# Schematics.net
KiCad netlist of a schematic drawn in Altium Designer
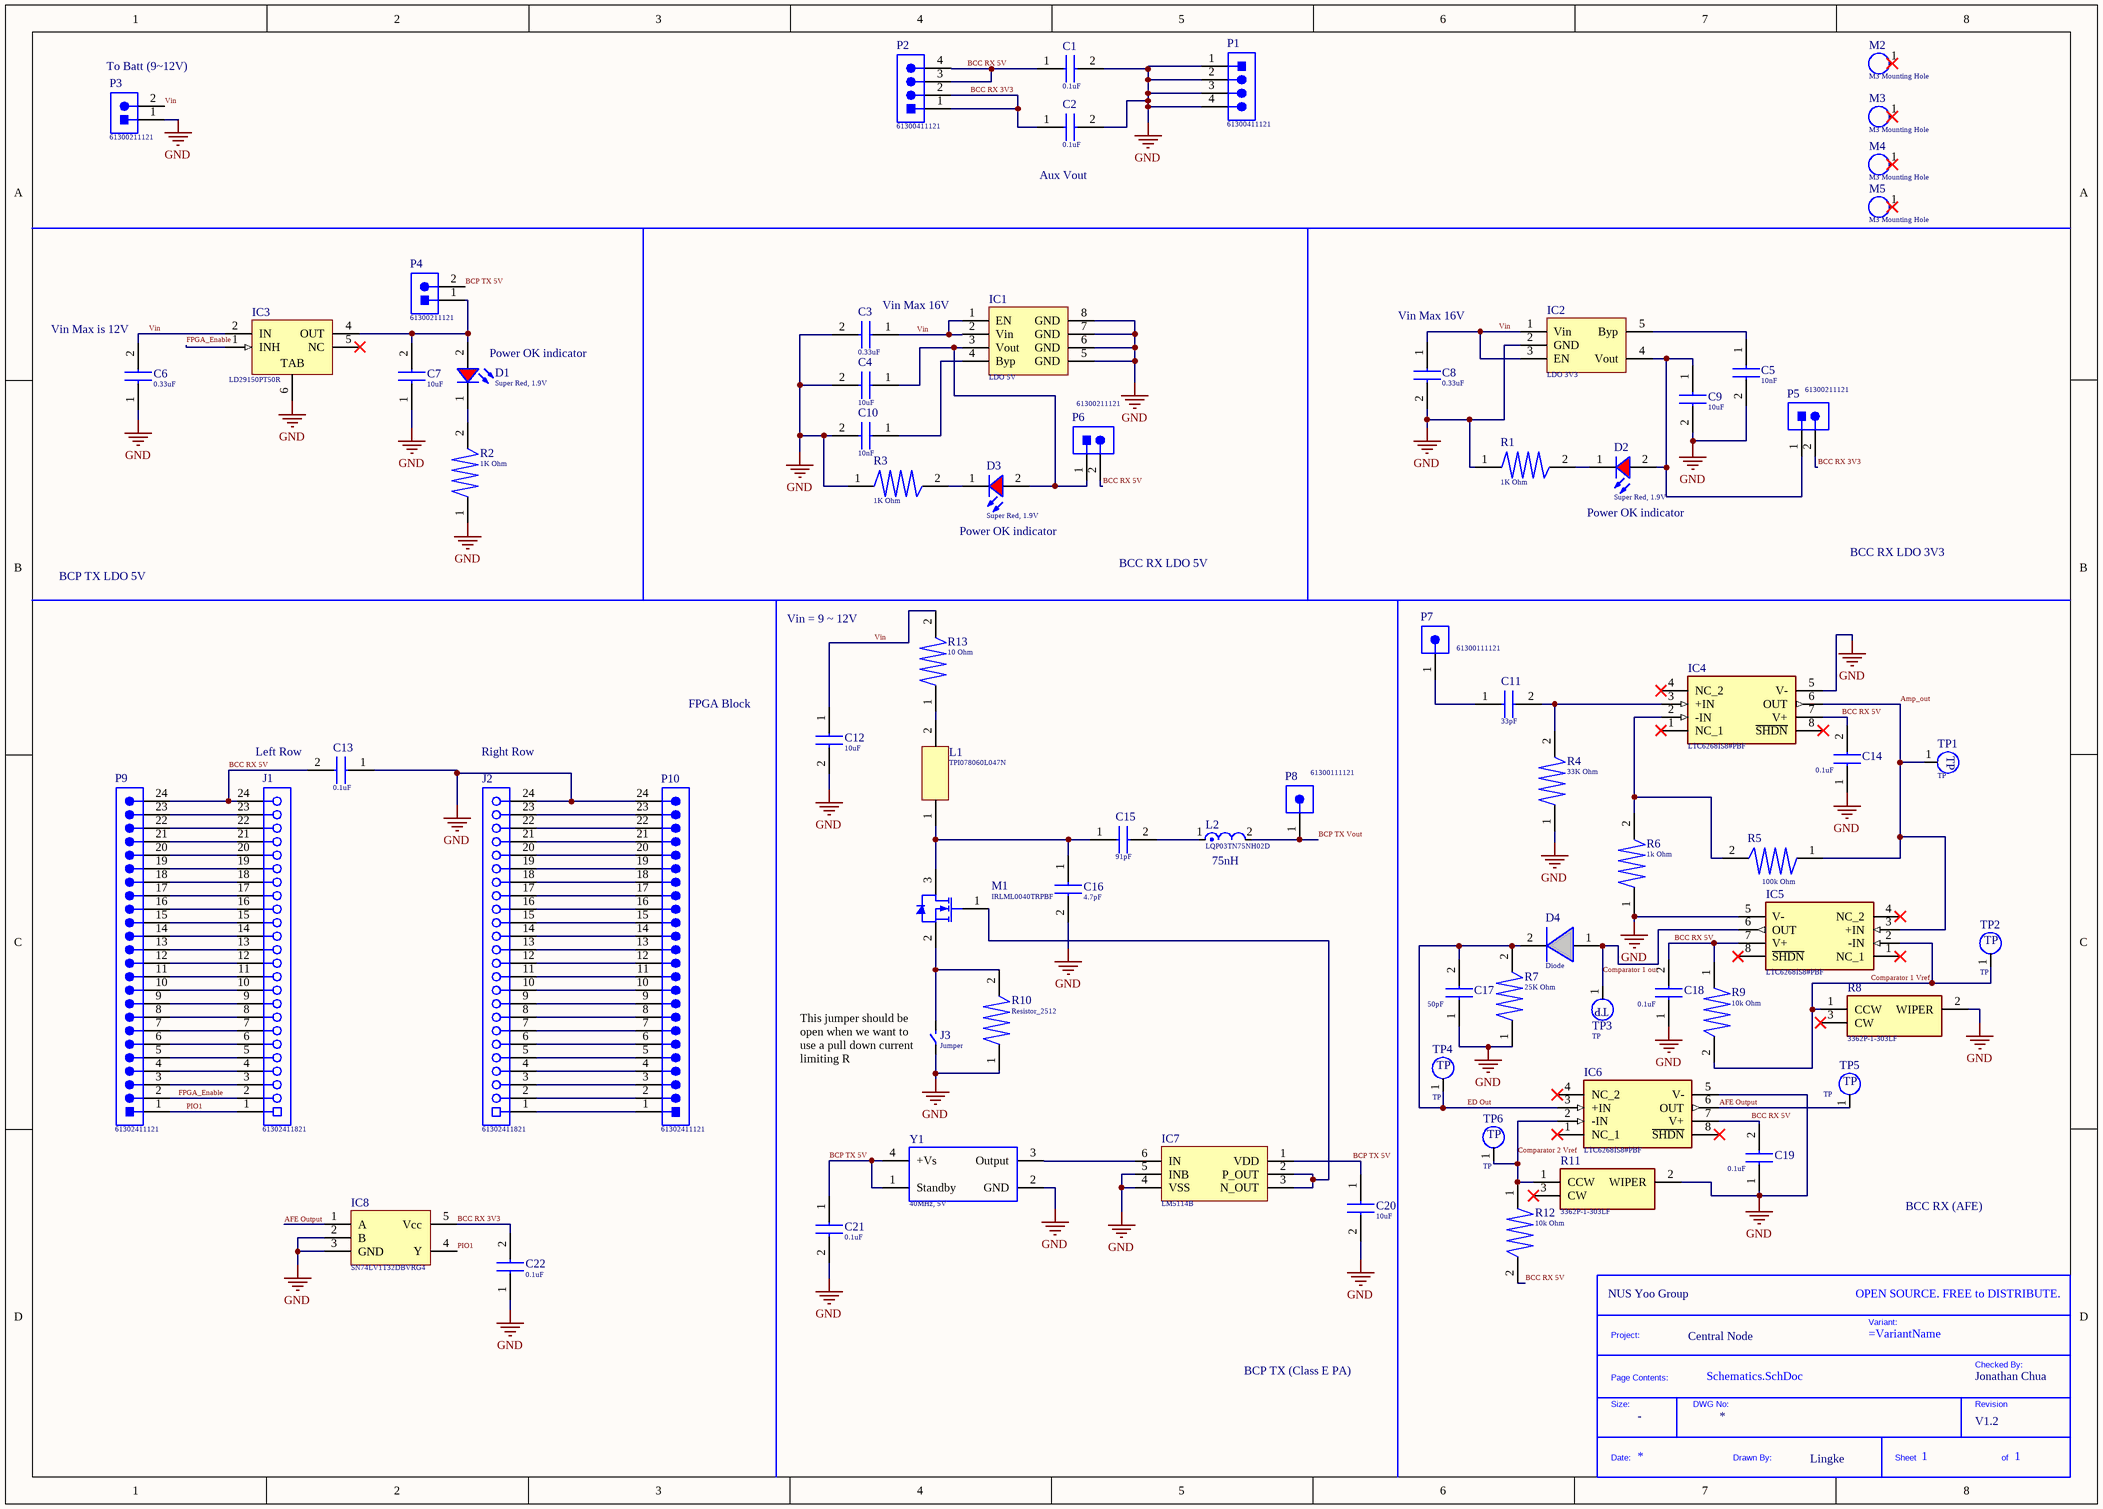
[diagram p0: Schematics.SchDoc]

(export (version "E")
  (design (tool "Eeschema 10.0.6"))
  (components
    (comp (ref "*")
      (value "Title_Block")
      (description "Standard Title Block.")
      (fields
        (field (name "PROJECT NAME") "Central Node")
        (field (name "COMPANY") "NUS Yoo Group")
        (field (name "DRAWN BY") "Lingke")
        (field (name "REVISION") "V1.2")
        (field (name "DWG NO") "*")
        (field (name "SIZE") "-")
        (field (name "CHECKED BY") "Jonathan Chua")
      )
      (libsource (lib "General Electronics") (part "Title_Block"))
    )
    (comp (ref "C1")
      (value "0.1uF")
      (footprint "0603")
      (description "Capacitor")
      (libsource (lib "General Electronics") (part "Capacitor_0603"))
    )
    (comp (ref "C2")
      (value "0.1uF")
      (footprint "0603")
      (description "Capacitor")
      (libsource (lib "General Electronics") (part "Capacitor_0603"))
    )
    (comp (ref "C3")
      (value "0.33uF")
      (footprint "0603")
      (description "Capacitor")
      (libsource (lib "General Electronics") (part "Capacitor_0603"))
    )
    (comp (ref "C4")
      (value "10uF")
      (footprint "0603")
      (description "Capacitor")
      (libsource (lib "General Electronics") (part "Capacitor_0603"))
    )
    (comp (ref "C5")
      (value "10nF")
      (footprint "0603")
      (description "Capacitor")
      (libsource (lib "General Electronics") (part "Capacitor_0603"))
    )
    (comp (ref "C6")
      (value "0.33uF")
      (footprint "0603")
      (description "Capacitor")
      (libsource (lib "General Electronics") (part "Capacitor_0603"))
    )
    (comp (ref "C7")
      (value "10uF")
      (footprint "0603")
      (description "Capacitor")
      (libsource (lib "General Electronics") (part "Capacitor_0603"))
    )
    (comp (ref "C8")
      (value "0.33uF")
      (footprint "0603")
      (description "Capacitor")
      (libsource (lib "General Electronics") (part "Capacitor_0603"))
    )
    (comp (ref "C9")
      (value "10uF")
      (footprint "0603")
      (description "Capacitor")
      (libsource (lib "General Electronics") (part "Capacitor_0603"))
    )
    (comp (ref "C10")
      (value "10nF")
      (footprint "0603")
      (description "Capacitor")
      (libsource (lib "General Electronics") (part "Capacitor_0603"))
    )
    (comp (ref "C11")
      (value "33pF")
      (footprint "0603")
      (description "Capacitor")
      (libsource (lib "General Electronics") (part "Capacitor_0603"))
    )
    (comp (ref "C12")
      (value "10uF")
      (footprint "0603")
      (description "Capacitor")
      (libsource (lib "General Electronics") (part "Capacitor_0603"))
    )
    (comp (ref "C13")
      (value "0.1uF")
      (footprint "0603")
      (description "Capacitor")
      (libsource (lib "General Electronics") (part "Capacitor_0603"))
    )
    (comp (ref "C14")
      (value "0.1uF")
      (footprint "0603")
      (description "Capacitor")
      (libsource (lib "General Electronics") (part "Capacitor_0603"))
    )
    (comp (ref "C15")
      (value "91pF")
      (footprint "0603")
      (description "Capacitor")
      (libsource (lib "General Electronics") (part "Capacitor_0603"))
    )
    (comp (ref "C16")
      (value "4.7pF")
      (footprint "0603")
      (description "Capacitor")
      (libsource (lib "General Electronics") (part "Capacitor_0603"))
    )
    (comp (ref "C17")
      (value "50pF")
      (footprint "0603")
      (description "Capacitor")
      (libsource (lib "General Electronics") (part "Capacitor_0603"))
    )
    (comp (ref "C18")
      (value "0.1uF")
      (footprint "0603")
      (description "Capacitor")
      (libsource (lib "General Electronics") (part "Capacitor_0603"))
    )
    (comp (ref "C19")
      (value "0.1uF")
      (footprint "0603")
      (description "Capacitor")
      (libsource (lib "General Electronics") (part "Capacitor_0603"))
    )
    (comp (ref "C20")
      (value "10uF")
      (footprint "0603")
      (description "Capacitor")
      (libsource (lib "General Electronics") (part "Capacitor_0603"))
    )
    (comp (ref "C21")
      (value "0.1uF")
      (footprint "0603")
      (description "Capacitor")
      (libsource (lib "General Electronics") (part "Capacitor_0603"))
    )
    (comp (ref "C22")
      (value "0.1uF")
      (footprint "0603")
      (description "Capacitor")
      (libsource (lib "General Electronics") (part "Capacitor_0603"))
    )
    (comp (ref "D1")
      (value "Super Red, 1.9V")
      (footprint "WL-SMCW_0603_H=0.7mm")
      (description "WL-SMCW SMT Mono-color Chip LED Waterclear, size 0603, Super Red, 1.9V, 140deg")
      (fields (field (name "PART NUMBER") "150060SS75000") (field (name "PUBLISHER") "Wurth Elektronik"))
      (libsource (lib "Altium_WL-SMCW (rev20a)") (part "150060SS75000"))
    )
    (comp (ref "D2")
      (value "Super Red, 1.9V")
      (footprint "WL-SMCW_0603_H=0.7mm")
      (description "WL-SMCW SMT Mono-color Chip LED Waterclear, size 0603, Super Red, 1.9V, 140deg")
      (fields (field (name "PART NUMBER") "150060SS75000") (field (name "PUBLISHER") "Wurth Elektronik"))
      (libsource (lib "Altium_WL-SMCW (rev20a)") (part "150060SS75000"))
    )
    (comp (ref "D3")
      (value "Super Red, 1.9V")
      (footprint "WL-SMCW_0603_H=0.7mm")
      (description "WL-SMCW SMT Mono-color Chip LED Waterclear, size 0603, Super Red, 1.9V, 140deg")
      (fields (field (name "PART NUMBER") "150060SS75000") (field (name "PUBLISHER") "Wurth Elektronik"))
      (libsource (lib "Altium_WL-SMCW (rev20a)") (part "150060SS75000"))
    )
    (comp (ref "D4") (value "Diode") (footprint "0603") (libsource (lib "FYP_BCC_BCP NUS") (part "Diode")))
    (comp (ref "IC1")
      (value "LDO 5V")
      (footprint "SOIC-8")
      (libsource (lib "FYP_BCC_BCP NUS") (part "SPX3819S-L-5-0/TR"))
    )
    (comp (ref "IC2")
      (value "LDO 3V3")
      (footprint "SOT-23-5")
      (libsource (lib "FYP_BCC_BCP NUS") (part "SPX3819M5-L-3-3/TR"))
    )
    (comp (ref "IC3")
      (value "LD29150PT50R")
      (footprint "PPAK_L")
      (description "1.5A, Very-Low Drop Voltage Regulator, 5V, 5-Pin PPAK")
      (libsource (lib "FYP_BCC_BCP NUS Symbol Library") (part "LD29150PT50R"))
    )
    (comp (ref "IC4")
      (value "LTC6268IS8#PBF")
      (footprint "SOIC127P599X175-8N")
      (description "Integrated Circuit")
      (fields (field (name "MOUSER2 PART NUMBER") "584-LTC6268IS8#PBF"))
      (libsource (lib "FYP_BCC_BCP NUS") (part "LTC6268IS8#PBF"))
    )
    (comp (ref "IC5")
      (value "LTC6268IS8#PBF")
      (footprint "SOIC127P599X175-8N")
      (description "Integrated Circuit")
      (fields (field (name "MOUSER2 PART NUMBER") "584-LTC6268IS8#PBF"))
      (libsource (lib "") (part "LTC6268IS8#PBF_1"))
    )
    (comp (ref "IC6")
      (value "LTC6268IS8#PBF")
      (footprint "SOIC127P599X175-8N")
      (description "Integrated Circuit")
      (fields (field (name "MOUSER2 PART NUMBER") "584-LTC6268IS8#PBF"))
      (libsource (lib "FYP_BCC_BCP NUS") (part "LTC6268IS8#PBF"))
    )
    (comp (ref "IC7")
      (value "LM5114B")
      (footprint "SOT-23-6")
      (libsource (lib "FYP_BCC_BCP NUS") (part "LM5114B"))
    )
    (comp (ref "IC8")
      (value "SN74LV1T32DBVRG4")
      (footprint "SOT-23-5")
      (libsource (lib "FYP_BCC_BCP NUS") (part "SN74LV1T32DBVRG4"))
    )
    (comp (ref "J1")
      (value "61302411821")
      (footprint "61302411821")
      (description "WR-PHD Socket Header, THT, pitch 2.54mm, Single Row, Vertical, 24p")
      (fields (field (name "MANUFACTURER") "Wurth Elektronik"))
      (libsource (lib "Altium_WR-PHD (rev22a)") (part "61302411821"))
    )
    (comp (ref "J2")
      (value "61302411821")
      (footprint "61302411821")
      (description "WR-PHD Socket Header, THT, pitch 2.54mm, Single Row, Vertical, 24p")
      (fields (field (name "MANUFACTURER") "Wurth Elektronik"))
      (libsource (lib "Altium_WR-PHD (rev22a)") (part "61302411821"))
    )
    (comp (ref "J3")
      (value "Jumper")
      (footprint "0603")
      (description "Capacitor")
      (libsource (lib "General Electronics") (part "0603_Jumper"))
    )
    (comp (ref "L1")
      (value "TPI078060L047N")
      (footprint "TPI078060L047N")
      (libsource (lib "FYP_BCC_BCP NUS") (part "TPI078060L047N"))
    )
    (comp (ref "L2")
      (value "LQP03TN75NH02D")
      (footprint "FP-LQP03PN_02-IPC_A")
      (description "Film type RF Inductor 75nH ±3% 100mA 10Ω 0201 (0603)")
      (fields (field (name "TOLERANCE") "3%"))
      (libsource (lib "FYP_BCC_BCP NUS") (part "LQP03TN75NH02D"))
    )
    (comp (ref "M1")
      (value "IRLML0040TRPBF")
      (footprint "SOT-23")
      (description "HEXFET(R) Power MOSFET, 40 V, -55 to 150 degC, 3-Pin SOT-23, RoHS, Tape and Reel")
      (fields (field (name "MANUFACTURER") "International Rectifier"))
      (libsource (lib "FYP_BCC_BCP NUS") (part "IRLML0040TRPBF"))
    )
    (comp (ref "M2")
      (value "M3 Mounting Hole")
      (footprint "M3 Hole")
      (libsource (lib "General Electronics") (part "M3_Mounting_hole"))
    )
    (comp (ref "M3")
      (value "M3 Mounting Hole")
      (footprint "M3 Hole")
      (libsource (lib "General Electronics") (part "M3_Mounting_hole"))
    )
    (comp (ref "M4")
      (value "M3 Mounting Hole")
      (footprint "M3 Hole")
      (libsource (lib "General Electronics") (part "M3_Mounting_hole"))
    )
    (comp (ref "M5")
      (value "M3 Mounting Hole")
      (footprint "M3 Hole")
      (libsource (lib "General Electronics") (part "M3_Mounting_hole"))
    )
    (comp (ref "P1")
      (value "61300411121")
      (footprint "61300411121")
      (description "WR-PHD Pin Header, THT, pitch 2.54mm, Single Row, Vertical, 4p")
      (fields (field (name "MANUFACTURER") "Wurth Elektronik"))
      (libsource (lib "") (part "61300411121_1"))
    )
    (comp (ref "P2")
      (value "61300411121")
      (footprint "61300411121")
      (description "WR-PHD Pin Header, THT, pitch 2.54mm, Single Row, Vertical, 4p")
      (fields (field (name "MANUFACTURER") "Wurth Elektronik"))
      (libsource (lib "Altium_WR-PHD (rev22a)") (part "61300411121"))
    )
    (comp (ref "P3")
      (value "61300211121")
      (footprint "61300211121")
      (description "WR-PHD Pin Header, THT, pitch 2.54mm, Single Row, Vertical, 2p")
      (fields (field (name "MANUFACTURER") "Wurth Elektronik"))
      (libsource (lib "Altium_WR-PHD (rev22a)") (part "61300211121"))
    )
    (comp (ref "P4")
      (value "61300211121")
      (footprint "61300211121")
      (description "WR-PHD Pin Header, THT, pitch 2.54mm, Single Row, Vertical, 2p")
      (fields (field (name "MANUFACTURER") "Wurth Elektronik"))
      (libsource (lib "Altium_WR-PHD (rev22a)") (part "61300211121"))
    )
    (comp (ref "P5")
      (value "61300211121")
      (footprint "61300211121")
      (description "WR-PHD Pin Header, THT, pitch 2.54mm, Single Row, Vertical, 2p")
      (fields (field (name "MANUFACTURER") "Wurth Elektronik"))
      (libsource (lib "") (part "61300211121_1"))
    )
    (comp (ref "P6")
      (value "61300211121")
      (footprint "61300211121")
      (description "WR-PHD Pin Header, THT, pitch 2.54mm, Single Row, Vertical, 2p")
      (fields (field (name "MANUFACTURER") "Wurth Elektronik"))
      (libsource (lib "") (part "61300211121_1"))
    )
    (comp (ref "P7")
      (value "61300111121")
      (footprint "61300111121")
      (description "WR-PHD Pin Header, THT, pitch 2.54mm, Single Row, Vertical, 1p")
      (fields (field (name "MANUFACTURER") "Wurth Elektronik"))
      (libsource (lib "Altium_WR-PHD (rev22a)") (part "61300111121"))
    )
    (comp (ref "P8")
      (value "61300111121")
      (footprint "61300111121")
      (description "WR-PHD Pin Header, THT, pitch 2.54mm, Single Row, Vertical, 1p")
      (fields (field (name "MANUFACTURER") "Wurth Elektronik"))
      (libsource (lib "Altium_WR-PHD (rev22a)") (part "61300111121"))
    )
    (comp (ref "P9")
      (value "61302411121")
      (footprint "61302411121")
      (description "WR-PHD Pin Header, THT, pitch 2.54mm, Single Row, Vertical, 24p")
      (fields (field (name "MANUFACTURER") "Wurth Elektronik"))
      (libsource (lib "Altium_WR-PHD (rev22a)") (part "61302411121"))
    )
    (comp (ref "P10")
      (value "61302411121")
      (footprint "61302411121")
      (description "WR-PHD Pin Header, THT, pitch 2.54mm, Single Row, Vertical, 24p")
      (fields (field (name "MANUFACTURER") "Wurth Elektronik"))
      (libsource (lib "Altium_WR-PHD (rev22a)") (part "61302411121"))
    )
    (comp (ref "R1")
      (value "1K Ohm")
      (footprint "0603")
      (description "Resistor")
      (libsource (lib "General Electronics") (part "Resistor"))
    )
    (comp (ref "R2")
      (value "1K Ohm")
      (footprint "0603")
      (description "Resistor")
      (libsource (lib "General Electronics") (part "Resistor"))
    )
    (comp (ref "R3")
      (value "1K Ohm")
      (footprint "0603")
      (description "Resistor")
      (libsource (lib "General Electronics") (part "Resistor"))
    )
    (comp (ref "R4")
      (value "33K Ohm")
      (footprint "0603")
      (description "Resistor")
      (libsource (lib "General Electronics") (part "Resistor"))
    )
    (comp (ref "R5")
      (value "100k Ohm")
      (footprint "0603")
      (description "Resistor")
      (libsource (lib "General Electronics") (part "Resistor"))
    )
    (comp (ref "R6")
      (value "1k Ohm")
      (footprint "0603")
      (description "Resistor")
      (libsource (lib "General Electronics") (part "Resistor"))
    )
    (comp (ref "R7")
      (value "25K Ohm")
      (footprint "0603")
      (description "Resistor")
      (libsource (lib "General Electronics") (part "Resistor"))
    )
    (comp (ref "R8")
      (value "3362P-1-303LF")
      (footprint "3362P_1")
      (description "Resistor")
      (libsource (lib "FYP_BCC_BCP NUS") (part "3362P-1-303LF"))
    )
    (comp (ref "R9")
      (value "10k Ohm")
      (footprint "0603")
      (description "Resistor")
      (libsource (lib "General Electronics") (part "Resistor"))
    )
    (comp (ref "R10")
      (value "Resistor_2512")
      (footprint "2512")
      (description "Resistor")
      (libsource (lib "General Electronics") (part "Resistor_2512"))
    )
    (comp (ref "R11")
      (value "3362P-1-303LF")
      (footprint "3362P_1")
      (description "Resistor")
      (libsource (lib "FYP_BCC_BCP NUS") (part "3362P-1-303LF"))
    )
    (comp (ref "R12")
      (value "10k Ohm")
      (footprint "0603")
      (description "Resistor")
      (libsource (lib "General Electronics") (part "Resistor"))
    )
    (comp (ref "R13")
      (value "10 Ohm")
      (footprint "2512")
      (description "Resistor")
      (libsource (lib "General Electronics") (part "Resistor_2512"))
    )
    (comp (ref "TP1")
      (value "TP")
      (footprint "Test Point")
      (description "Test Point 1mm by 1mm")
      (libsource (lib "General Electronics") (part "Test Point"))
    )
    (comp (ref "TP2")
      (value "TP")
      (footprint "Test Point")
      (description "Test Point 1mm by 1mm")
      (libsource (lib "General Electronics") (part "Test Point"))
    )
    (comp (ref "TP3")
      (value "TP")
      (footprint "Test Point")
      (description "Test Point 1mm by 1mm")
      (libsource (lib "General Electronics") (part "Test Point"))
    )
    (comp (ref "TP4")
      (value "TP")
      (footprint "Test Point")
      (description "Test Point 1mm by 1mm")
      (libsource (lib "General Electronics") (part "Test Point"))
    )
    (comp (ref "TP5")
      (value "TP")
      (footprint "Test Point")
      (description "Test Point 1mm by 1mm")
      (libsource (lib "General Electronics") (part "Test Point"))
    )
    (comp (ref "TP6")
      (value "TP")
      (footprint "Test Point")
      (description "Test Point 1mm by 1mm")
      (libsource (lib "General Electronics") (part "Test Point"))
    )
    (comp (ref "Y1")
      (value "40MHz, 5V")
      (footprint "WE-SPXO_CFPS-72")
      (description "WE-SPXO Simple Packaged Quartz Oscillator, SMT, CFPS-72, 40MHz, 5V")
      (fields
        (field (name "MANUFACTURER") "Wurth Elektronik")
        (field (name "MANUFACTURER PART NUMBER") "831018739")
      )
      (libsource (lib "Altium_WE-SPXO (rev20c)") (part "831018739"))
    )
  )
  (nets
    (net (code "1") (name "/AFE Output") (class "Default")
      (node (ref "IC6") (pin "6") (pinfunction "OUT_6") (pintype "output"))
      (node (ref "IC8") (pin "1") (pinfunction "A_1") (pintype "passive"))
      (node (ref "TP5") (pin "1") (pinfunction "TP_1") (pintype "passive"))
    )
    (net (code "2") (name "/Amp_out") (class "Default")
      (node (ref "IC4") (pin "6") (pinfunction "OUT_6") (pintype "output"))
      (node (ref "IC5") (pin "3") (pinfunction "+IN_3") (pintype "input"))
      (node (ref "R5") (pin "1") (pintype "passive"))
      (node (ref "TP1") (pin "1") (pinfunction "TP_1") (pintype "passive"))
    )
    (net (code "3") (name "/BCC RX 3V3") (class "Default")
      (node (ref "C2") (pin "1") (pinfunction "1_1") (pintype "passive"))
      (node (ref "C22") (pin "2") (pinfunction "2_2") (pintype "passive"))
      (node (ref "IC8") (pin "5") (pinfunction "Vcc_5") (pintype "passive"))
      (node (ref "P2") (pin "1") (pinfunction "1_1") (pintype "passive"))
      (node (ref "P2") (pin "2") (pinfunction "2_2") (pintype "passive"))
      (node (ref "P5") (pin "2") (pinfunction "2_2") (pintype "passive"))
    )
    (net (code "4") (name "/BCC RX 5V") (class "Default")
      (node (ref "C1") (pin "1") (pinfunction "1_1") (pintype "passive"))
      (node (ref "C13") (pin "2") (pinfunction "2_2") (pintype "passive"))
      (node (ref "C14") (pin "2") (pinfunction "2_2") (pintype "passive"))
      (node (ref "C18") (pin "2") (pinfunction "2_2") (pintype "passive"))
      (node (ref "C19") (pin "2") (pinfunction "2_2") (pintype "passive"))
      (node (ref "IC4") (pin "7") (pinfunction "V+_7") (pintype "passive"))
      (node (ref "IC5") (pin "7") (pinfunction "V+_7") (pintype "passive"))
      (node (ref "IC6") (pin "7") (pinfunction "V+_7") (pintype "passive"))
      (node (ref "J1") (pin "24") (pinfunction "24_24") (pintype "passive"))
      (node (ref "P2") (pin "3") (pinfunction "3_3") (pintype "passive"))
      (node (ref "P2") (pin "4") (pinfunction "4_4") (pintype "passive"))
      (node (ref "P6") (pin "2") (pinfunction "2_2") (pintype "passive"))
      (node (ref "P9") (pin "24") (pinfunction "24_24") (pintype "passive"))
      (node (ref "R12") (pin "2") (pintype "passive"))
      (node (ref "R9") (pin "1") (pintype "passive"))
    )
    (net (code "5") (name "/BCP TX 5V") (class "Default")
      (node (ref "C20") (pin "1") (pinfunction "1_1") (pintype "passive"))
      (node (ref "C21") (pin "1") (pinfunction "1_1") (pintype "passive"))
      (node (ref "IC7") (pin "1") (pinfunction "VDD_1") (pintype "passive"))
      (node (ref "P4") (pin "2") (pinfunction "2_2") (pintype "passive"))
      (node (ref "Y1") (pin "1") (pinfunction "Standby_1") (pintype "passive"))
      (node (ref "Y1") (pin "4") (pinfunction "+Vs_4") (pintype "passive"))
    )
    (net (code "6") (name "/BCP TX Vout") (class "Default")
      (node (ref "L2") (pin "2") (pinfunction "2_2") (pintype "passive"))
      (node (ref "P8") (pin "1") (pinfunction "1_1") (pintype "passive"))
    )
    (net (code "7") (name "/Comparator 1 Vref") (class "Default")
      (node (ref "IC5") (pin "2") (pinfunction "-IN_2") (pintype "input"))
      (node (ref "R8") (pin "1") (pinfunction "CCW_1") (pintype "passive"))
      (node (ref "R9") (pin "2") (pintype "passive"))
      (node (ref "TP2") (pin "1") (pinfunction "TP_1") (pintype "passive"))
    )
    (net (code "8") (name "/Comparator 1 out") (class "Default")
      (node (ref "D4") (pin "1") (pintype "passive"))
      (node (ref "IC5") (pin "6") (pinfunction "OUT_6") (pintype "output"))
      (node (ref "TP3") (pin "1") (pinfunction "TP_1") (pintype "passive"))
    )
    (net (code "9") (name "/Comparator 2 Vref") (class "Default")
      (node (ref "IC6") (pin "2") (pinfunction "-IN_2") (pintype "input"))
      (node (ref "R11") (pin "1") (pinfunction "CCW_1") (pintype "passive"))
      (node (ref "R12") (pin "1") (pintype "passive"))
      (node (ref "TP6") (pin "1") (pinfunction "TP_1") (pintype "passive"))
    )
    (net (code "10") (name "/ED Out") (class "Default")
      (node (ref "C17") (pin "2") (pinfunction "2_2") (pintype "passive"))
      (node (ref "D4") (pin "2") (pintype "passive"))
      (node (ref "IC6") (pin "3") (pinfunction "+IN_3") (pintype "input"))
      (node (ref "R7") (pin "2") (pintype "passive"))
      (node (ref "TP4") (pin "1") (pinfunction "TP_1") (pintype "passive"))
    )
    (net (code "11") (name "/FPGA_Enable") (class "Default")
      (node (ref "IC3") (pin "1") (pinfunction "INH_1") (pintype "input"))
      (node (ref "J1") (pin "2") (pinfunction "2_2") (pintype "passive"))
      (node (ref "P9") (pin "2") (pinfunction "2_2") (pintype "passive"))
    )
    (net (code "12") (name "/PIO1") (class "Default")
      (node (ref "IC8") (pin "4") (pinfunction "Y_4") (pintype "passive"))
      (node (ref "J1") (pin "1") (pinfunction "1_1") (pintype "passive"))
      (node (ref "P9") (pin "1") (pinfunction "1_1") (pintype "passive"))
    )
    (net (code "13") (name "/Vin") (class "Default")
      (node (ref "C12") (pin "1") (pinfunction "1_1") (pintype "passive"))
      (node (ref "C3") (pin "1") (pinfunction "1_1") (pintype "passive"))
      (node (ref "C6") (pin "2") (pinfunction "2_2") (pintype "passive"))
      (node (ref "C8") (pin "1") (pinfunction "1_1") (pintype "passive"))
      (node (ref "IC1") (pin "1") (pinfunction "EN_1") (pintype "passive"))
      (node (ref "IC1") (pin "2") (pinfunction "Vin_2") (pintype "passive"))
      (node (ref "IC2") (pin "1") (pinfunction "Vin_1") (pintype "passive"))
      (node (ref "IC2") (pin "3") (pinfunction "EN_3") (pintype "passive"))
      (node (ref "IC3") (pin "2") (pinfunction "IN_2") (pintype "power_in"))
      (node (ref "P3") (pin "2") (pinfunction "2_2") (pintype "passive"))
      (node (ref "R13") (pin "2") (pintype "passive"))
    )
    (net (code "14") (name "GND") (class "Default")
      (node (ref "C1") (pin "2") (pinfunction "2_2") (pintype "passive"))
      (node (ref "C10") (pin "2") (pinfunction "2_2") (pintype "passive"))
      (node (ref "C12") (pin "2") (pinfunction "2_2") (pintype "passive"))
      (node (ref "C13") (pin "1") (pinfunction "1_1") (pintype "passive"))
      (node (ref "C14") (pin "1") (pinfunction "1_1") (pintype "passive"))
      (node (ref "C16") (pin "2") (pinfunction "2_2") (pintype "passive"))
      (node (ref "C17") (pin "1") (pinfunction "1_1") (pintype "passive"))
      (node (ref "C18") (pin "1") (pinfunction "1_1") (pintype "passive"))
      (node (ref "C19") (pin "1") (pinfunction "1_1") (pintype "passive"))
      (node (ref "C2") (pin "2") (pinfunction "2_2") (pintype "passive"))
      (node (ref "C20") (pin "2") (pinfunction "2_2") (pintype "passive"))
      (node (ref "C21") (pin "2") (pinfunction "2_2") (pintype "passive"))
      (node (ref "C22") (pin "1") (pinfunction "1_1") (pintype "passive"))
      (node (ref "C3") (pin "2") (pinfunction "2_2") (pintype "passive"))
      (node (ref "C4") (pin "2") (pinfunction "2_2") (pintype "passive"))
      (node (ref "C5") (pin "2") (pinfunction "2_2") (pintype "passive"))
      (node (ref "C6") (pin "1") (pinfunction "1_1") (pintype "passive"))
      (node (ref "C7") (pin "1") (pinfunction "1_1") (pintype "passive"))
      (node (ref "C8") (pin "2") (pinfunction "2_2") (pintype "passive"))
      (node (ref "C9") (pin "2") (pinfunction "2_2") (pintype "passive"))
      (node (ref "IC1") (pin "5") (pinfunction "GND_5") (pintype "passive"))
      (node (ref "IC1") (pin "6") (pinfunction "GND_6") (pintype "passive"))
      (node (ref "IC1") (pin "7") (pinfunction "GND_7") (pintype "passive"))
      (node (ref "IC1") (pin "8") (pinfunction "GND_8") (pintype "passive"))
      (node (ref "IC2") (pin "2") (pinfunction "GND_2") (pintype "passive"))
      (node (ref "IC3") (pin "6") (pinfunction "TAB_6") (pintype "passive"))
      (node (ref "IC4") (pin "5") (pinfunction "V-_5") (pintype "passive"))
      (node (ref "IC5") (pin "5") (pinfunction "V-_5") (pintype "passive"))
      (node (ref "IC6") (pin "5") (pinfunction "V-_5") (pintype "passive"))
      (node (ref "IC7") (pin "4") (pinfunction "VSS_4") (pintype "passive"))
      (node (ref "IC7") (pin "5") (pinfunction "INB_5") (pintype "passive"))
      (node (ref "IC8") (pin "2") (pinfunction "B_2") (pintype "passive"))
      (node (ref "IC8") (pin "3") (pinfunction "GND_3") (pintype "passive"))
      (node (ref "J2") (pin "24") (pinfunction "24_24") (pintype "passive"))
      (node (ref "J3") (pin "1") (pinfunction "1_1") (pintype "passive"))
      (node (ref "P1") (pin "1") (pinfunction "1_1") (pintype "passive"))
      (node (ref "P1") (pin "2") (pinfunction "2_2") (pintype "passive"))
      (node (ref "P1") (pin "3") (pinfunction "3_3") (pintype "passive"))
      (node (ref "P1") (pin "4") (pinfunction "4_4") (pintype "passive"))
      (node (ref "P10") (pin "24") (pinfunction "24_24") (pintype "passive"))
      (node (ref "P3") (pin "1") (pinfunction "1_1") (pintype "passive"))
      (node (ref "R1") (pin "1") (pintype "passive"))
      (node (ref "R10") (pin "1") (pintype "passive"))
      (node (ref "R11") (pin "2") (pinfunction "WIPER_2") (pintype "passive"))
      (node (ref "R2") (pin "1") (pintype "passive"))
      (node (ref "R3") (pin "1") (pintype "passive"))
      (node (ref "R4") (pin "1") (pintype "passive"))
      (node (ref "R6") (pin "1") (pintype "passive"))
      (node (ref "R7") (pin "1") (pintype "passive"))
      (node (ref "R8") (pin "2") (pinfunction "WIPER_2") (pintype "passive"))
      (node (ref "Y1") (pin "2") (pinfunction "GND_2") (pintype "passive"))
    )
    (net (code "15") (name "Net-(C11-Pad1)") (class "Default")
      (node (ref "C11") (pin "1") (pinfunction "1_1") (pintype "passive"))
      (node (ref "P7") (pin "1") (pinfunction "1_1") (pintype "passive"))
    )
    (net (code "16") (name "Net-(C15-Pad2)") (class "Default")
      (node (ref "C15") (pin "2") (pinfunction "2_2") (pintype "passive"))
      (node (ref "L2") (pin "1") (pinfunction "1_1") (pintype "passive"))
    )
    (net (code "17") (name "Net-(D1-A)") (class "Default")
      (node (ref "C7") (pin "2") (pinfunction "2_2") (pintype "passive"))
      (node (ref "D1") (pin "2") (pinfunction "A_2") (pintype "passive"))
      (node (ref "IC3") (pin "4") (pinfunction "OUT_4") (pintype "power_in"))
      (node (ref "P4") (pin "1") (pinfunction "1_1") (pintype "passive"))
    )
    (net (code "18") (name "Net-(D1-K)") (class "Default")
      (node (ref "D1") (pin "1") (pinfunction "K_1") (pintype "passive"))
      (node (ref "R2") (pin "2") (pintype "passive"))
    )
    (net (code "19") (name "Net-(D2-A)") (class "Default")
      (node (ref "C9") (pin "1") (pinfunction "1_1") (pintype "passive"))
      (node (ref "D2") (pin "2") (pinfunction "A_2") (pintype "passive"))
      (node (ref "IC2") (pin "4") (pinfunction "Vout_4") (pintype "passive"))
      (node (ref "P5") (pin "1") (pinfunction "1_1") (pintype "passive"))
    )
    (net (code "20") (name "Net-(D2-K)") (class "Default")
      (node (ref "D2") (pin "1") (pinfunction "K_1") (pintype "passive"))
      (node (ref "R1") (pin "2") (pintype "passive"))
    )
    (net (code "21") (name "Net-(D3-A)") (class "Default")
      (node (ref "C4") (pin "1") (pinfunction "1_1") (pintype "passive"))
      (node (ref "D3") (pin "2") (pinfunction "A_2") (pintype "passive"))
      (node (ref "IC1") (pin "3") (pinfunction "Vout_3") (pintype "passive"))
      (node (ref "P6") (pin "1") (pinfunction "1_1") (pintype "passive"))
    )
    (net (code "22") (name "Net-(D3-K)") (class "Default")
      (node (ref "D3") (pin "1") (pinfunction "K_1") (pintype "passive"))
      (node (ref "R3") (pin "2") (pintype "passive"))
    )
    (net (code "23") (name "Net-(IC1-Byp)") (class "Default")
      (node (ref "C10") (pin "1") (pinfunction "1_1") (pintype "passive"))
      (node (ref "IC1") (pin "4") (pinfunction "Byp_4") (pintype "passive"))
    )
    (net (code "24") (name "Net-(IC2-Byp)") (class "Default")
      (node (ref "C5") (pin "1") (pinfunction "1_1") (pintype "passive"))
      (node (ref "IC2") (pin "5") (pinfunction "Byp_5") (pintype "passive"))
    )
    (net (code "25") (name "Net-(IC4-+IN)") (class "Default")
      (node (ref "C11") (pin "2") (pinfunction "2_2") (pintype "passive"))
      (node (ref "IC4") (pin "3") (pinfunction "+IN_3") (pintype "input"))
      (node (ref "R4") (pin "2") (pintype "passive"))
    )
    (net (code "26") (name "Net-(IC4--IN)") (class "Default")
      (node (ref "IC4") (pin "2") (pinfunction "-IN_2") (pintype "input"))
      (node (ref "R5") (pin "2") (pintype "passive"))
      (node (ref "R6") (pin "2") (pintype "passive"))
    )
    (net (code "27") (name "Net-(IC7-IN)") (class "Default")
      (node (ref "IC7") (pin "6") (pinfunction "IN_6") (pintype "passive"))
      (node (ref "Y1") (pin "3") (pinfunction "Output_3") (pintype "passive"))
    )
    (net (code "28") (name "Net-(IC7-N_OUT)") (class "Default")
      (node (ref "IC7") (pin "2") (pinfunction "P_OUT_2") (pintype "passive"))
      (node (ref "IC7") (pin "3") (pinfunction "N_OUT_3") (pintype "passive"))
      (node (ref "M1") (pin "1") (pinfunction "G_1") (pintype "passive"))
    )
    (net (code "29") (name "Net-(J1-Pad3)") (class "Default")
      (node (ref "J1") (pin "3") (pinfunction "3_3") (pintype "passive"))
      (node (ref "P9") (pin "3") (pinfunction "3_3") (pintype "passive"))
    )
    (net (code "30") (name "Net-(J1-Pad4)") (class "Default")
      (node (ref "J1") (pin "4") (pinfunction "4_4") (pintype "passive"))
      (node (ref "P9") (pin "4") (pinfunction "4_4") (pintype "passive"))
    )
    (net (code "31") (name "Net-(J1-Pad5)") (class "Default")
      (node (ref "J1") (pin "5") (pinfunction "5_5") (pintype "passive"))
      (node (ref "P9") (pin "5") (pinfunction "5_5") (pintype "passive"))
    )
    (net (code "32") (name "Net-(J1-Pad6)") (class "Default")
      (node (ref "J1") (pin "6") (pinfunction "6_6") (pintype "passive"))
      (node (ref "P9") (pin "6") (pinfunction "6_6") (pintype "passive"))
    )
    (net (code "33") (name "Net-(J1-Pad7)") (class "Default")
      (node (ref "J1") (pin "7") (pinfunction "7_7") (pintype "passive"))
      (node (ref "P9") (pin "7") (pinfunction "7_7") (pintype "passive"))
    )
    (net (code "34") (name "Net-(J1-Pad8)") (class "Default")
      (node (ref "J1") (pin "8") (pinfunction "8_8") (pintype "passive"))
      (node (ref "P9") (pin "8") (pinfunction "8_8") (pintype "passive"))
    )
    (net (code "35") (name "Net-(J1-Pad9)") (class "Default")
      (node (ref "J1") (pin "9") (pinfunction "9_9") (pintype "passive"))
      (node (ref "P9") (pin "9") (pinfunction "9_9") (pintype "passive"))
    )
    (net (code "36") (name "Net-(J1-Pad10)") (class "Default")
      (node (ref "J1") (pin "10") (pinfunction "10_10") (pintype "passive"))
      (node (ref "P9") (pin "10") (pinfunction "10_10") (pintype "passive"))
    )
    (net (code "37") (name "Net-(J1-Pad11)") (class "Default")
      (node (ref "J1") (pin "11") (pinfunction "11_11") (pintype "passive"))
      (node (ref "P9") (pin "11") (pinfunction "11_11") (pintype "passive"))
    )
    (net (code "38") (name "Net-(J1-Pad12)") (class "Default")
      (node (ref "J1") (pin "12") (pinfunction "12_12") (pintype "passive"))
      (node (ref "P9") (pin "12") (pinfunction "12_12") (pintype "passive"))
    )
    (net (code "39") (name "Net-(J1-Pad13)") (class "Default")
      (node (ref "J1") (pin "13") (pinfunction "13_13") (pintype "passive"))
      (node (ref "P9") (pin "13") (pinfunction "13_13") (pintype "passive"))
    )
    (net (code "40") (name "Net-(J1-Pad14)") (class "Default")
      (node (ref "J1") (pin "14") (pinfunction "14_14") (pintype "passive"))
      (node (ref "P9") (pin "14") (pinfunction "14_14") (pintype "passive"))
    )
    (net (code "41") (name "Net-(J1-Pad15)") (class "Default")
      (node (ref "J1") (pin "15") (pinfunction "15_15") (pintype "passive"))
      (node (ref "P9") (pin "15") (pinfunction "15_15") (pintype "passive"))
    )
    (net (code "42") (name "Net-(J1-Pad16)") (class "Default")
      (node (ref "J1") (pin "16") (pinfunction "16_16") (pintype "passive"))
      (node (ref "P9") (pin "16") (pinfunction "16_16") (pintype "passive"))
    )
    (net (code "43") (name "Net-(J1-Pad17)") (class "Default")
      (node (ref "J1") (pin "17") (pinfunction "17_17") (pintype "passive"))
      (node (ref "P9") (pin "17") (pinfunction "17_17") (pintype "passive"))
    )
    (net (code "44") (name "Net-(J1-Pad18)") (class "Default")
      (node (ref "J1") (pin "18") (pinfunction "18_18") (pintype "passive"))
      (node (ref "P9") (pin "18") (pinfunction "18_18") (pintype "passive"))
    )
    (net (code "45") (name "Net-(J1-Pad19)") (class "Default")
      (node (ref "J1") (pin "19") (pinfunction "19_19") (pintype "passive"))
      (node (ref "P9") (pin "19") (pinfunction "19_19") (pintype "passive"))
    )
    (net (code "46") (name "Net-(J1-Pad20)") (class "Default")
      (node (ref "J1") (pin "20") (pinfunction "20_20") (pintype "passive"))
      (node (ref "P9") (pin "20") (pinfunction "20_20") (pintype "passive"))
    )
    (net (code "47") (name "Net-(J1-Pad21)") (class "Default")
      (node (ref "J1") (pin "21") (pinfunction "21_21") (pintype "passive"))
      (node (ref "P9") (pin "21") (pinfunction "21_21") (pintype "passive"))
    )
    (net (code "48") (name "Net-(J1-Pad22)") (class "Default")
      (node (ref "J1") (pin "22") (pinfunction "22_22") (pintype "passive"))
      (node (ref "P9") (pin "22") (pinfunction "22_22") (pintype "passive"))
    )
    (net (code "49") (name "Net-(J1-Pad23)") (class "Default")
      (node (ref "J1") (pin "23") (pinfunction "23_23") (pintype "passive"))
      (node (ref "P9") (pin "23") (pinfunction "23_23") (pintype "passive"))
    )
    (net (code "50") (name "Net-(J2-Pad1)") (class "Default")
      (node (ref "J2") (pin "1") (pinfunction "1_1") (pintype "passive"))
      (node (ref "P10") (pin "1") (pinfunction "1_1") (pintype "passive"))
    )
    (net (code "51") (name "Net-(J2-Pad2)") (class "Default")
      (node (ref "J2") (pin "2") (pinfunction "2_2") (pintype "passive"))
      (node (ref "P10") (pin "2") (pinfunction "2_2") (pintype "passive"))
    )
    (net (code "52") (name "Net-(J2-Pad3)") (class "Default")
      (node (ref "J2") (pin "3") (pinfunction "3_3") (pintype "passive"))
      (node (ref "P10") (pin "3") (pinfunction "3_3") (pintype "passive"))
    )
    (net (code "53") (name "Net-(J2-Pad4)") (class "Default")
      (node (ref "J2") (pin "4") (pinfunction "4_4") (pintype "passive"))
      (node (ref "P10") (pin "4") (pinfunction "4_4") (pintype "passive"))
    )
    (net (code "54") (name "Net-(J2-Pad5)") (class "Default")
      (node (ref "J2") (pin "5") (pinfunction "5_5") (pintype "passive"))
      (node (ref "P10") (pin "5") (pinfunction "5_5") (pintype "passive"))
    )
    (net (code "55") (name "Net-(J2-Pad6)") (class "Default")
      (node (ref "J2") (pin "6") (pinfunction "6_6") (pintype "passive"))
      (node (ref "P10") (pin "6") (pinfunction "6_6") (pintype "passive"))
    )
    (net (code "56") (name "Net-(J2-Pad7)") (class "Default")
      (node (ref "J2") (pin "7") (pinfunction "7_7") (pintype "passive"))
      (node (ref "P10") (pin "7") (pinfunction "7_7") (pintype "passive"))
    )
    (net (code "57") (name "Net-(J2-Pad8)") (class "Default")
      (node (ref "J2") (pin "8") (pinfunction "8_8") (pintype "passive"))
      (node (ref "P10") (pin "8") (pinfunction "8_8") (pintype "passive"))
    )
    (net (code "58") (name "Net-(J2-Pad9)") (class "Default")
      (node (ref "J2") (pin "9") (pinfunction "9_9") (pintype "passive"))
      (node (ref "P10") (pin "9") (pinfunction "9_9") (pintype "passive"))
    )
    (net (code "59") (name "Net-(J2-Pad10)") (class "Default")
      (node (ref "J2") (pin "10") (pinfunction "10_10") (pintype "passive"))
      (node (ref "P10") (pin "10") (pinfunction "10_10") (pintype "passive"))
    )
    (net (code "60") (name "Net-(J2-Pad11)") (class "Default")
      (node (ref "J2") (pin "11") (pinfunction "11_11") (pintype "passive"))
      (node (ref "P10") (pin "11") (pinfunction "11_11") (pintype "passive"))
    )
    (net (code "61") (name "Net-(J2-Pad12)") (class "Default")
      (node (ref "J2") (pin "12") (pinfunction "12_12") (pintype "passive"))
      (node (ref "P10") (pin "12") (pinfunction "12_12") (pintype "passive"))
    )
    (net (code "62") (name "Net-(J2-Pad13)") (class "Default")
      (node (ref "J2") (pin "13") (pinfunction "13_13") (pintype "passive"))
      (node (ref "P10") (pin "13") (pinfunction "13_13") (pintype "passive"))
    )
    (net (code "63") (name "Net-(J2-Pad14)") (class "Default")
      (node (ref "J2") (pin "14") (pinfunction "14_14") (pintype "passive"))
      (node (ref "P10") (pin "14") (pinfunction "14_14") (pintype "passive"))
    )
    (net (code "64") (name "Net-(J2-Pad15)") (class "Default")
      (node (ref "J2") (pin "15") (pinfunction "15_15") (pintype "passive"))
      (node (ref "P10") (pin "15") (pinfunction "15_15") (pintype "passive"))
    )
    (net (code "65") (name "Net-(J2-Pad16)") (class "Default")
      (node (ref "J2") (pin "16") (pinfunction "16_16") (pintype "passive"))
      (node (ref "P10") (pin "16") (pinfunction "16_16") (pintype "passive"))
    )
    (net (code "66") (name "Net-(J2-Pad17)") (class "Default")
      (node (ref "J2") (pin "17") (pinfunction "17_17") (pintype "passive"))
      (node (ref "P10") (pin "17") (pinfunction "17_17") (pintype "passive"))
    )
    (net (code "67") (name "Net-(J2-Pad18)") (class "Default")
      (node (ref "J2") (pin "18") (pinfunction "18_18") (pintype "passive"))
      (node (ref "P10") (pin "18") (pinfunction "18_18") (pintype "passive"))
    )
    (net (code "68") (name "Net-(J2-Pad19)") (class "Default")
      (node (ref "J2") (pin "19") (pinfunction "19_19") (pintype "passive"))
      (node (ref "P10") (pin "19") (pinfunction "19_19") (pintype "passive"))
    )
    (net (code "69") (name "Net-(J2-Pad20)") (class "Default")
      (node (ref "J2") (pin "20") (pinfunction "20_20") (pintype "passive"))
      (node (ref "P10") (pin "20") (pinfunction "20_20") (pintype "passive"))
    )
    (net (code "70") (name "Net-(J2-Pad21)") (class "Default")
      (node (ref "J2") (pin "21") (pinfunction "21_21") (pintype "passive"))
      (node (ref "P10") (pin "21") (pinfunction "21_21") (pintype "passive"))
    )
    (net (code "71") (name "Net-(J2-Pad22)") (class "Default")
      (node (ref "J2") (pin "22") (pinfunction "22_22") (pintype "passive"))
      (node (ref "P10") (pin "22") (pinfunction "22_22") (pintype "passive"))
    )
    (net (code "72") (name "Net-(J2-Pad23)") (class "Default")
      (node (ref "J2") (pin "23") (pinfunction "23_23") (pintype "passive"))
      (node (ref "P10") (pin "23") (pinfunction "23_23") (pintype "passive"))
    )
    (net (code "73") (name "Net-(L1-Pad2)") (class "Default")
      (node (ref "L1") (pin "2") (pintype "passive"))
      (node (ref "R13") (pin "1") (pintype "passive"))
    )
    (net (code "74") (name "Net-(M1-D)") (class "Default")
      (node (ref "C15") (pin "1") (pinfunction "1_1") (pintype "passive"))
      (node (ref "C16") (pin "1") (pinfunction "1_1") (pintype "passive"))
      (node (ref "L1") (pin "1") (pintype "passive"))
      (node (ref "M1") (pin "3") (pinfunction "D_3") (pintype "passive"))
    )
    (net (code "75") (name "Net-(M1-S)") (class "Default")
      (node (ref "J3") (pin "2") (pinfunction "2_2") (pintype "passive"))
      (node (ref "M1") (pin "2") (pinfunction "S_2") (pintype "passive"))
      (node (ref "R10") (pin "2") (pintype "passive"))
    )
    (net (code "76") (name "unconnected-(IC3-NC-Pad5)") (class "Default")
      (node (ref "IC3") (pin "5") (pinfunction "NC_5") (pintype "passive+no_connect"))
    )
    (net (code "77") (name "unconnected-(IC4-NC_1-Pad1)") (class "Default")
      (node (ref "IC4") (pin "1") (pinfunction "NC_1_1") (pintype "passive+no_connect"))
    )
    (net (code "78") (name "unconnected-(IC4-NC_2-Pad4)") (class "Default")
      (node (ref "IC4") (pin "4") (pinfunction "NC_2_4") (pintype "passive+no_connect"))
    )
    (net (code "79") (name "unconnected-(IC4-~{SHDN}-Pad8)") (class "Default")
      (node (ref "IC4") (pin "8") (pinfunction "~{SHDN}_8") (pintype "passive+no_connect"))
    )
    (net (code "80") (name "unconnected-(IC5-NC_1-Pad1)") (class "Default")
      (node (ref "IC5") (pin "1") (pinfunction "NC_1_1") (pintype "passive+no_connect"))
    )
    (net (code "81") (name "unconnected-(IC5-NC_2-Pad4)") (class "Default")
      (node (ref "IC5") (pin "4") (pinfunction "NC_2_4") (pintype "passive+no_connect"))
    )
    (net (code "82") (name "unconnected-(IC5-~{SHDN}-Pad8)") (class "Default")
      (node (ref "IC5") (pin "8") (pinfunction "~{SHDN}_8") (pintype "passive+no_connect"))
    )
    (net (code "83") (name "unconnected-(IC6-NC_1-Pad1)") (class "Default")
      (node (ref "IC6") (pin "1") (pinfunction "NC_1_1") (pintype "passive+no_connect"))
    )
    (net (code "84") (name "unconnected-(IC6-NC_2-Pad4)") (class "Default")
      (node (ref "IC6") (pin "4") (pinfunction "NC_2_4") (pintype "passive+no_connect"))
    )
    (net (code "85") (name "unconnected-(IC6-~{SHDN}-Pad8)") (class "Default")
      (node (ref "IC6") (pin "8") (pinfunction "~{SHDN}_8") (pintype "passive+no_connect"))
    )
    (net (code "86") (name "unconnected-(M2-Pad1)") (class "Default")
      (node (ref "M2") (pin "1") (pinfunction "1_1") (pintype "passive+no_connect"))
    )
    (net (code "87") (name "unconnected-(M3-Pad1)") (class "Default")
      (node (ref "M3") (pin "1") (pinfunction "1_1") (pintype "passive+no_connect"))
    )
    (net (code "88") (name "unconnected-(M4-Pad1)") (class "Default")
      (node (ref "M4") (pin "1") (pinfunction "1_1") (pintype "passive+no_connect"))
    )
    (net (code "89") (name "unconnected-(M5-Pad1)") (class "Default")
      (node (ref "M5") (pin "1") (pinfunction "1_1") (pintype "passive+no_connect"))
    )
    (net (code "90") (name "unconnected-(R8-CW-Pad3)") (class "Default")
      (node (ref "R8") (pin "3") (pinfunction "CW_3") (pintype "passive+no_connect"))
    )
    (net (code "91") (name "unconnected-(R11-CW-Pad3)") (class "Default")
      (node (ref "R11") (pin "3") (pinfunction "CW_3") (pintype "passive+no_connect"))
    )
  )
)
